# FMCLPCConnector.net
KiCad netlist of a schematic drawn in Altium Designer
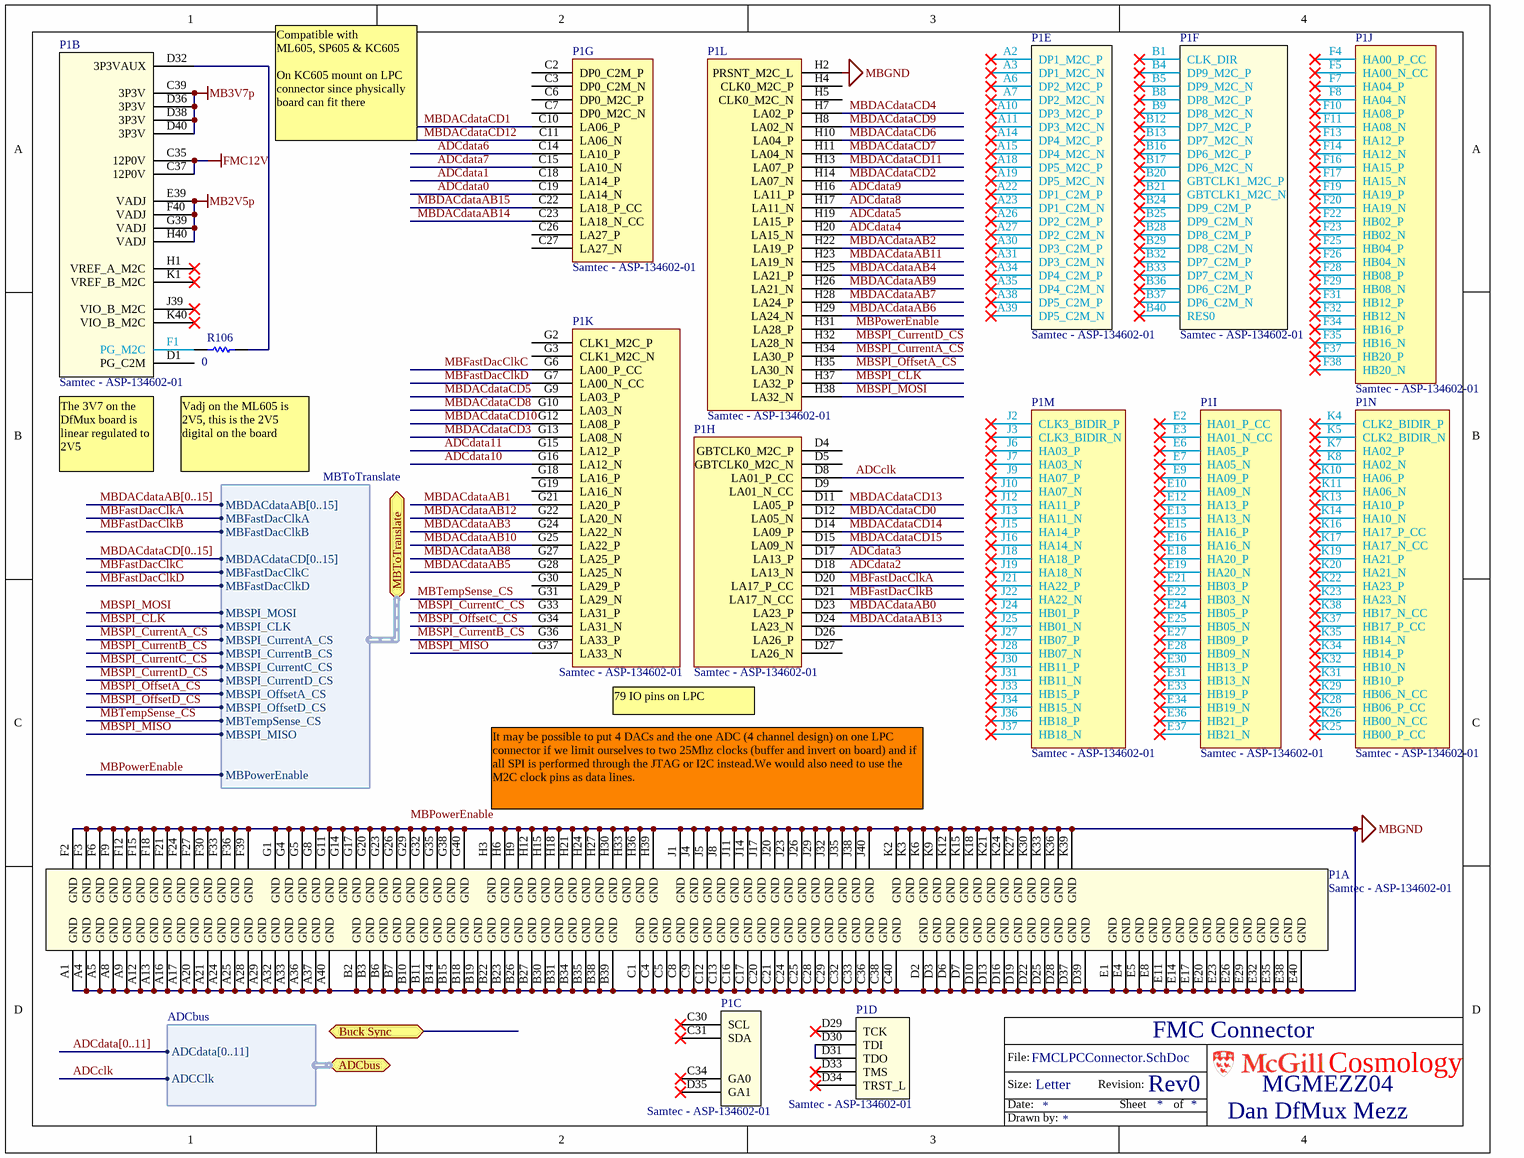
[diagram p0: FMCLPCConnector.SchDoc]

(export (version "E")
  (design (tool "Eeschema 10.0.6"))
  (components
    (comp (ref "P1")
      (value "Samtec - ASP-134602-01")
      (footprint "BTB-SM1-27-2V400M")
      (description "Samtec ASP-134602-01")
      (libsource (lib "MGMEZZ04") (part "Samtec - ASP-134602-01"))
    )
    (comp (ref "R106")
      (value "0")
      (footprint "0603")
      (description "Resistor")
      (fields (field (name "MANUFACTURER") "Generic"))
      (libsource (lib "MGMEZZ04") (part "RES 0603"))
    )
  )
  (nets
    (net (code "3") (name "/ADCclk") (class "Default")
      (node (ref "P1") (pin "D8") (pinfunction "LA01_P_CC_D8") (pintype "passive"))
    )
    (net (code "4") (name "/ADCdata0") (class "Default")
      (node (ref "P1") (pin "C19") (pinfunction "LA14_N_C19") (pintype "passive"))
    )
    (net (code "5") (name "/ADCdata1") (class "Default")
      (node (ref "P1") (pin "C18") (pinfunction "LA14_P_C18") (pintype "passive"))
    )
    (net (code "6") (name "/ADCdata2") (class "Default")
      (node (ref "P1") (pin "D18") (pinfunction "LA13_N_D18") (pintype "passive"))
    )
    (net (code "7") (name "/ADCdata3") (class "Default")
      (node (ref "P1") (pin "D17") (pinfunction "LA13_P_D17") (pintype "passive"))
    )
    (net (code "8") (name "/ADCdata4") (class "Default")
      (node (ref "P1") (pin "H20") (pinfunction "LA15_N_H20") (pintype "passive"))
    )
    (net (code "9") (name "/ADCdata5") (class "Default")
      (node (ref "P1") (pin "H19") (pinfunction "LA15_P_H19") (pintype "passive"))
    )
    (net (code "10") (name "/ADCdata6") (class "Default")
      (node (ref "P1") (pin "C14") (pinfunction "LA10_P_C14") (pintype "passive"))
    )
    (net (code "11") (name "/ADCdata7") (class "Default")
      (node (ref "P1") (pin "C15") (pinfunction "LA10_N_C15") (pintype "passive"))
    )
    (net (code "12") (name "/ADCdata8") (class "Default")
      (node (ref "P1") (pin "H17") (pinfunction "LA11_N_H17") (pintype "passive"))
    )
    (net (code "13") (name "/ADCdata9") (class "Default")
      (node (ref "P1") (pin "H16") (pinfunction "LA11_P_H16") (pintype "passive"))
    )
    (net (code "14") (name "/ADCdata10") (class "Default")
      (node (ref "P1") (pin "G16") (pinfunction "LA12_N_G16") (pintype "passive"))
    )
    (net (code "15") (name "/ADCdata11") (class "Default")
      (node (ref "P1") (pin "G15") (pinfunction "LA12_P_G15") (pintype "passive"))
    )
    (net (code "18") (name "/MBDACdataAB0") (class "Default")
      (node (ref "P1") (pin "D23") (pinfunction "LA23_P_D23") (pintype "passive"))
    )
    (net (code "19") (name "/MBDACdataAB1") (class "Default")
      (node (ref "P1") (pin "G21") (pinfunction "LA20_P_G21") (pintype "passive"))
    )
    (net (code "20") (name "/MBDACdataAB2") (class "Default")
      (node (ref "P1") (pin "H22") (pinfunction "LA19_P_H22") (pintype "passive"))
    )
    (net (code "21") (name "/MBDACdataAB3") (class "Default")
      (node (ref "P1") (pin "G24") (pinfunction "LA22_N_G24") (pintype "passive"))
    )
    (net (code "22") (name "/MBDACdataAB4") (class "Default")
      (node (ref "P1") (pin "H25") (pinfunction "LA21_P_H25") (pintype "passive"))
    )
    (net (code "23") (name "/MBDACdataAB5") (class "Default")
      (node (ref "P1") (pin "G28") (pinfunction "LA25_N_G28") (pintype "passive"))
    )
    (net (code "24") (name "/MBDACdataAB6") (class "Default")
      (node (ref "P1") (pin "H29") (pinfunction "LA24_N_H29") (pintype "passive"))
    )
    (net (code "25") (name "/MBDACdataAB7") (class "Default")
      (node (ref "P1") (pin "H28") (pinfunction "LA24_P_H28") (pintype "passive"))
    )
    (net (code "26") (name "/MBDACdataAB8") (class "Default")
      (node (ref "P1") (pin "G27") (pinfunction "LA25_P_G27") (pintype "passive"))
    )
    (net (code "27") (name "/MBDACdataAB9") (class "Default")
      (node (ref "P1") (pin "H26") (pinfunction "LA21_N_H26") (pintype "passive"))
    )
    (net (code "28") (name "/MBDACdataAB10") (class "Default")
      (node (ref "P1") (pin "G25") (pinfunction "LA22_P_G25") (pintype "passive"))
    )
    (net (code "29") (name "/MBDACdataAB11") (class "Default")
      (node (ref "P1") (pin "H23") (pinfunction "LA19_N_H23") (pintype "passive"))
    )
    (net (code "30") (name "/MBDACdataAB12") (class "Default")
      (node (ref "P1") (pin "G22") (pinfunction "LA20_N_G22") (pintype "passive"))
    )
    (net (code "31") (name "/MBDACdataAB13") (class "Default")
      (node (ref "P1") (pin "D24") (pinfunction "LA23_N_D24") (pintype "passive"))
    )
    (net (code "32") (name "/MBDACdataAB14") (class "Default")
      (node (ref "P1") (pin "C23") (pinfunction "LA18_N_CC_C23") (pintype "passive"))
    )
    (net (code "33") (name "/MBDACdataAB15") (class "Default")
      (node (ref "P1") (pin "C22") (pinfunction "LA18_P_CC_C22") (pintype "passive"))
    )
    (net (code "35") (name "/MBDACdataCD0") (class "Default")
      (node (ref "P1") (pin "D12") (pinfunction "LA05_N_D12") (pintype "passive"))
    )
    (net (code "36") (name "/MBDACdataCD1") (class "Default")
      (node (ref "P1") (pin "C10") (pinfunction "LA06_P_C10") (pintype "passive"))
    )
    (net (code "37") (name "/MBDACdataCD2") (class "Default")
      (node (ref "P1") (pin "H14") (pinfunction "LA07_N_H14") (pintype "passive"))
    )
    (net (code "38") (name "/MBDACdataCD3") (class "Default")
      (node (ref "P1") (pin "G13") (pinfunction "LA08_N_G13") (pintype "passive"))
    )
    (net (code "39") (name "/MBDACdataCD4") (class "Default")
      (node (ref "P1") (pin "H7") (pinfunction "LA02_P_H7") (pintype "passive"))
    )
    (net (code "40") (name "/MBDACdataCD5") (class "Default")
      (node (ref "P1") (pin "G9") (pinfunction "LA03_P_G9") (pintype "passive"))
    )
    (net (code "41") (name "/MBDACdataCD6") (class "Default")
      (node (ref "P1") (pin "H10") (pinfunction "LA04_P_H10") (pintype "passive"))
    )
    (net (code "42") (name "/MBDACdataCD7") (class "Default")
      (node (ref "P1") (pin "H11") (pinfunction "LA04_N_H11") (pintype "passive"))
    )
    (net (code "43") (name "/MBDACdataCD8") (class "Default")
      (node (ref "P1") (pin "G10") (pinfunction "LA03_N_G10") (pintype "passive"))
    )
    (net (code "44") (name "/MBDACdataCD9") (class "Default")
      (node (ref "P1") (pin "H8") (pinfunction "LA02_N_H8") (pintype "passive"))
    )
    (net (code "45") (name "/MBDACdataCD10") (class "Default")
      (node (ref "P1") (pin "G12") (pinfunction "LA08_P_G12") (pintype "passive"))
    )
    (net (code "46") (name "/MBDACdataCD11") (class "Default")
      (node (ref "P1") (pin "H13") (pinfunction "LA07_P_H13") (pintype "passive"))
    )
    (net (code "47") (name "/MBDACdataCD12") (class "Default")
      (node (ref "P1") (pin "C11") (pinfunction "LA06_N_C11") (pintype "passive"))
    )
    (net (code "48") (name "/MBDACdataCD13") (class "Default")
      (node (ref "P1") (pin "D11") (pinfunction "LA05_P_D11") (pintype "passive"))
    )
    (net (code "49") (name "/MBDACdataCD14") (class "Default")
      (node (ref "P1") (pin "D14") (pinfunction "LA09_P_D14") (pintype "passive"))
    )
    (net (code "50") (name "/MBDACdataCD15") (class "Default")
      (node (ref "P1") (pin "D15") (pinfunction "LA09_N_D15") (pintype "passive"))
    )
    (net (code "52") (name "/MBFastDacClkA") (class "Default")
      (node (ref "P1") (pin "D20") (pinfunction "LA17_P_CC_D20") (pintype "passive"))
    )
    (net (code "53") (name "/MBFastDacClkB") (class "Default")
      (node (ref "P1") (pin "D21") (pinfunction "LA17_N_CC_D21") (pintype "passive"))
    )
    (net (code "54") (name "/MBFastDacClkC") (class "Default")
      (node (ref "P1") (pin "G6") (pinfunction "LA00_P_CC_G6") (pintype "passive"))
    )
    (net (code "55") (name "/MBFastDacClkD") (class "Default")
      (node (ref "P1") (pin "G7") (pinfunction "LA00_N_CC_G7") (pintype "passive"))
    )
    (net (code "56") (name "/MBPowerEnable") (class "Default")
      (node (ref "P1") (pin "H31") (pinfunction "LA28_P_H31") (pintype "passive"))
    )
    (net (code "57") (name "/MBSPI_CLK") (class "Default")
      (node (ref "P1") (pin "H37") (pinfunction "LA32_P_H37") (pintype "passive"))
    )
    (net (code "58") (name "/MBSPI_CurrentA_CS") (class "Default")
      (node (ref "P1") (pin "H34") (pinfunction "LA30_P_H34") (pintype "passive"))
    )
    (net (code "59") (name "/MBSPI_CurrentB_CS") (class "Default")
      (node (ref "P1") (pin "G36") (pinfunction "LA33_P_G36") (pintype "passive"))
    )
    (net (code "60") (name "/MBSPI_CurrentC_CS") (class "Default")
      (node (ref "P1") (pin "G33") (pinfunction "LA31_P_G33") (pintype "passive"))
    )
    (net (code "61") (name "/MBSPI_CurrentD_CS") (class "Default")
      (node (ref "P1") (pin "H32") (pinfunction "LA28_N_H32") (pintype "passive"))
    )
    (net (code "62") (name "/MBSPI_MISO") (class "Default")
      (node (ref "P1") (pin "G37") (pinfunction "LA33_N_G37") (pintype "passive"))
    )
    (net (code "63") (name "/MBSPI_MOSI") (class "Default")
      (node (ref "P1") (pin "H38") (pinfunction "LA32_N_H38") (pintype "passive"))
    )
    (net (code "64") (name "/MBSPI_OffsetA_CS") (class "Default")
      (node (ref "P1") (pin "H35") (pinfunction "LA30_N_H35") (pintype "passive"))
    )
    (net (code "65") (name "/MBSPI_OffsetC_CS") (class "Default")
      (node (ref "P1") (pin "G34") (pinfunction "LA31_N_G34") (pintype "passive"))
    )
    (net (code "67") (name "/MBTempSense_CS") (class "Default")
      (node (ref "P1") (pin "G31") (pinfunction "LA29_N_G31") (pintype "passive"))
    )
    (net (code "70") (name "FMC12V") (class "Default")
      (node (ref "P1") (pin "C35") (pinfunction "12P0V_C35") (pintype "passive"))
      (node (ref "P1") (pin "C37") (pinfunction "12P0V_C37") (pintype "passive"))
    )
    (net (code "71") (name "MB2V5p") (class "Default")
      (node (ref "P1") (pin "E39") (pinfunction "VADJ_E39") (pintype "passive"))
      (node (ref "P1") (pin "F40") (pinfunction "VADJ_F40") (pintype "passive"))
      (node (ref "P1") (pin "G39") (pinfunction "VADJ_G39") (pintype "passive"))
      (node (ref "P1") (pin "H40") (pinfunction "VADJ_H40") (pintype "passive"))
    )
    (net (code "72") (name "MB3V7p") (class "Default")
      (node (ref "P1") (pin "C39") (pinfunction "3P3V_C39") (pintype "passive"))
      (node (ref "P1") (pin "D36") (pinfunction "3P3V_D36") (pintype "passive"))
      (node (ref "P1") (pin "D38") (pinfunction "3P3V_D38") (pintype "passive"))
      (node (ref "P1") (pin "D40") (pinfunction "3P3V_D40") (pintype "passive"))
    )
    (net (code "73") (name "MBGND") (class "Default")
      (node (ref "P1") (pin "A1") (pinfunction "GND_A1") (pintype "passive"))
      (node (ref "P1") (pin "A12") (pinfunction "GND_A12") (pintype "passive"))
      (node (ref "P1") (pin "A13") (pinfunction "GND_A13") (pintype "passive"))
      (node (ref "P1") (pin "A16") (pinfunction "GND_A16") (pintype "passive"))
      (node (ref "P1") (pin "A17") (pinfunction "GND_A17") (pintype "passive"))
      (node (ref "P1") (pin "A20") (pinfunction "GND_A20") (pintype "passive"))
      (node (ref "P1") (pin "A21") (pinfunction "GND_A21") (pintype "passive"))
      (node (ref "P1") (pin "A24") (pinfunction "GND_A24") (pintype "passive"))
      (node (ref "P1") (pin "A25") (pinfunction "GND_A25") (pintype "passive"))
      (node (ref "P1") (pin "A28") (pinfunction "GND_A28") (pintype "passive"))
      (node (ref "P1") (pin "A29") (pinfunction "GND_A29") (pintype "passive"))
      (node (ref "P1") (pin "A32") (pinfunction "GND_A32") (pintype "passive"))
      (node (ref "P1") (pin "A33") (pinfunction "GND_A33") (pintype "passive"))
      (node (ref "P1") (pin "A36") (pinfunction "GND_A36") (pintype "passive"))
      (node (ref "P1") (pin "A37") (pinfunction "GND_A37") (pintype "passive"))
      (node (ref "P1") (pin "A4") (pinfunction "GND_A4") (pintype "passive"))
      (node (ref "P1") (pin "A40") (pinfunction "GND_A40") (pintype "passive"))
      (node (ref "P1") (pin "A5") (pinfunction "GND_A5") (pintype "passive"))
      (node (ref "P1") (pin "A8") (pinfunction "GND_A8") (pintype "passive"))
      (node (ref "P1") (pin "A9") (pinfunction "GND_A9") (pintype "passive"))
      (node (ref "P1") (pin "B10") (pinfunction "GND_B10") (pintype "passive"))
      (node (ref "P1") (pin "B11") (pinfunction "GND_B11") (pintype "passive"))
      (node (ref "P1") (pin "B14") (pinfunction "GND_B14") (pintype "passive"))
      (node (ref "P1") (pin "B15") (pinfunction "GND_B15") (pintype "passive"))
      (node (ref "P1") (pin "B18") (pinfunction "GND_B18") (pintype "passive"))
      (node (ref "P1") (pin "B19") (pinfunction "GND_B19") (pintype "passive"))
      (node (ref "P1") (pin "B2") (pinfunction "GND_B2") (pintype "passive"))
      (node (ref "P1") (pin "B22") (pinfunction "GND_B22") (pintype "passive"))
      (node (ref "P1") (pin "B23") (pinfunction "GND_B23") (pintype "passive"))
      (node (ref "P1") (pin "B26") (pinfunction "GND_B26") (pintype "passive"))
      (node (ref "P1") (pin "B27") (pinfunction "GND_B27") (pintype "passive"))
      (node (ref "P1") (pin "B3") (pinfunction "GND_B3") (pintype "passive"))
      (node (ref "P1") (pin "B30") (pinfunction "GND_B30") (pintype "passive"))
      (node (ref "P1") (pin "B31") (pinfunction "GND_B31") (pintype "passive"))
      (node (ref "P1") (pin "B34") (pinfunction "GND_B34") (pintype "passive"))
      (node (ref "P1") (pin "B35") (pinfunction "GND_B35") (pintype "passive"))
      (node (ref "P1") (pin "B38") (pinfunction "GND_B38") (pintype "passive"))
      (node (ref "P1") (pin "B39") (pinfunction "GND_B39") (pintype "passive"))
      (node (ref "P1") (pin "B6") (pinfunction "GND_B6") (pintype "passive"))
      (node (ref "P1") (pin "B7") (pinfunction "GND_B7") (pintype "passive"))
      (node (ref "P1") (pin "C1") (pinfunction "GND_C1") (pintype "passive"))
      (node (ref "P1") (pin "C12") (pinfunction "GND_C12") (pintype "passive"))
      (node (ref "P1") (pin "C13") (pinfunction "GND_C13") (pintype "passive"))
      (node (ref "P1") (pin "C16") (pinfunction "GND_C16") (pintype "passive"))
      (node (ref "P1") (pin "C17") (pinfunction "GND_C17") (pintype "passive"))
      (node (ref "P1") (pin "C20") (pinfunction "GND_C20") (pintype "passive"))
      (node (ref "P1") (pin "C21") (pinfunction "GND_C21") (pintype "passive"))
      (node (ref "P1") (pin "C24") (pinfunction "GND_C24") (pintype "passive"))
      (node (ref "P1") (pin "C25") (pinfunction "GND_C25") (pintype "passive"))
      (node (ref "P1") (pin "C28") (pinfunction "GND_C28") (pintype "passive"))
      (node (ref "P1") (pin "C29") (pinfunction "GND_C29") (pintype "passive"))
      (node (ref "P1") (pin "C32") (pinfunction "GND_C32") (pintype "passive"))
      (node (ref "P1") (pin "C33") (pinfunction "GND_C33") (pintype "passive"))
      (node (ref "P1") (pin "C36") (pinfunction "GND_C36") (pintype "passive"))
      (node (ref "P1") (pin "C38") (pinfunction "GND_C38") (pintype "passive"))
      (node (ref "P1") (pin "C4") (pinfunction "GND_C4") (pintype "passive"))
      (node (ref "P1") (pin "C40") (pinfunction "GND_C40") (pintype "passive"))
      (node (ref "P1") (pin "C5") (pinfunction "GND_C5") (pintype "passive"))
      (node (ref "P1") (pin "C8") (pinfunction "GND_C8") (pintype "passive"))
      (node (ref "P1") (pin "C9") (pinfunction "GND_C9") (pintype "passive"))
      (node (ref "P1") (pin "D10") (pinfunction "GND_D10") (pintype "passive"))
      (node (ref "P1") (pin "D13") (pinfunction "GND_D13") (pintype "passive"))
      (node (ref "P1") (pin "D16") (pinfunction "GND_D16") (pintype "passive"))
      (node (ref "P1") (pin "D19") (pinfunction "GND_D19") (pintype "passive"))
      (node (ref "P1") (pin "D2") (pinfunction "GND_D2") (pintype "passive"))
      (node (ref "P1") (pin "D22") (pinfunction "GND_D22") (pintype "passive"))
      (node (ref "P1") (pin "D25") (pinfunction "GND_D25") (pintype "passive"))
      (node (ref "P1") (pin "D28") (pinfunction "GND_D28") (pintype "passive"))
      (node (ref "P1") (pin "D3") (pinfunction "GND_D3") (pintype "passive"))
      (node (ref "P1") (pin "D37") (pinfunction "GND_D37") (pintype "passive"))
      (node (ref "P1") (pin "D39") (pinfunction "GND_D39") (pintype "passive"))
      (node (ref "P1") (pin "D6") (pinfunction "GND_D6") (pintype "passive"))
      (node (ref "P1") (pin "D7") (pinfunction "GND_D7") (pintype "passive"))
      (node (ref "P1") (pin "E1") (pinfunction "GND_E1") (pintype "passive"))
      (node (ref "P1") (pin "E11") (pinfunction "GND_E11") (pintype "passive"))
      (node (ref "P1") (pin "E14") (pinfunction "GND_E14") (pintype "passive"))
      (node (ref "P1") (pin "E17") (pinfunction "GND_E17") (pintype "passive"))
      (node (ref "P1") (pin "E20") (pinfunction "GND_E20") (pintype "passive"))
      (node (ref "P1") (pin "E23") (pinfunction "GND_E23") (pintype "passive"))
      (node (ref "P1") (pin "E26") (pinfunction "GND_E26") (pintype "passive"))
      (node (ref "P1") (pin "E29") (pinfunction "GND_E29") (pintype "passive"))
      (node (ref "P1") (pin "E32") (pinfunction "GND_E32") (pintype "passive"))
      (node (ref "P1") (pin "E35") (pinfunction "GND_E35") (pintype "passive"))
      (node (ref "P1") (pin "E38") (pinfunction "GND_E38") (pintype "passive"))
      (node (ref "P1") (pin "E4") (pinfunction "GND_E4") (pintype "passive"))
      (node (ref "P1") (pin "E40") (pinfunction "GND_E40") (pintype "passive"))
      (node (ref "P1") (pin "E5") (pinfunction "GND_E5") (pintype "passive"))
      (node (ref "P1") (pin "E8") (pinfunction "GND_E8") (pintype "passive"))
      (node (ref "P1") (pin "F12") (pinfunction "GND_F12") (pintype "passive"))
      (node (ref "P1") (pin "F15") (pinfunction "GND_F15") (pintype "passive"))
      (node (ref "P1") (pin "F18") (pinfunction "GND_F18") (pintype "passive"))
      (node (ref "P1") (pin "F2") (pinfunction "GND_F2") (pintype "passive"))
      (node (ref "P1") (pin "F21") (pinfunction "GND_F21") (pintype "passive"))
      (node (ref "P1") (pin "F24") (pinfunction "GND_F24") (pintype "passive"))
      (node (ref "P1") (pin "F27") (pinfunction "GND_F27") (pintype "passive"))
      (node (ref "P1") (pin "F3") (pinfunction "GND_F3") (pintype "passive"))
      (node (ref "P1") (pin "F30") (pinfunction "GND_F30") (pintype "passive"))
      (node (ref "P1") (pin "F33") (pinfunction "GND_F33") (pintype "passive"))
      (node (ref "P1") (pin "F36") (pinfunction "GND_F36") (pintype "passive"))
      (node (ref "P1") (pin "F39") (pinfunction "GND_F39") (pintype "passive"))
      (node (ref "P1") (pin "F6") (pinfunction "GND_F6") (pintype "passive"))
      (node (ref "P1") (pin "F9") (pinfunction "GND_F9") (pintype "passive"))
      (node (ref "P1") (pin "G1") (pinfunction "GND_G1") (pintype "passive"))
      (node (ref "P1") (pin "G11") (pinfunction "GND_G11") (pintype "passive"))
      (node (ref "P1") (pin "G14") (pinfunction "GND_G14") (pintype "passive"))
      (node (ref "P1") (pin "G17") (pinfunction "GND_G17") (pintype "passive"))
      (node (ref "P1") (pin "G20") (pinfunction "GND_G20") (pintype "passive"))
      (node (ref "P1") (pin "G23") (pinfunction "GND_G23") (pintype "passive"))
      (node (ref "P1") (pin "G26") (pinfunction "GND_G26") (pintype "passive"))
      (node (ref "P1") (pin "G29") (pinfunction "GND_G29") (pintype "passive"))
      (node (ref "P1") (pin "G32") (pinfunction "GND_G32") (pintype "passive"))
      (node (ref "P1") (pin "G35") (pinfunction "GND_G35") (pintype "passive"))
      (node (ref "P1") (pin "G38") (pinfunction "GND_G38") (pintype "passive"))
      (node (ref "P1") (pin "G4") (pinfunction "GND_G4") (pintype "passive"))
      (node (ref "P1") (pin "G40") (pinfunction "GND_G40") (pintype "passive"))
      (node (ref "P1") (pin "G5") (pinfunction "GND_G5") (pintype "passive"))
      (node (ref "P1") (pin "G8") (pinfunction "GND_G8") (pintype "passive"))
      (node (ref "P1") (pin "H12") (pinfunction "GND_H12") (pintype "passive"))
      (node (ref "P1") (pin "H15") (pinfunction "GND_H15") (pintype "passive"))
      (node (ref "P1") (pin "H18") (pinfunction "GND_H18") (pintype "passive"))
      (node (ref "P1") (pin "H2") (pinfunction "PRSNT_M2C_L_H2") (pintype "passive"))
      (node (ref "P1") (pin "H21") (pinfunction "GND_H21") (pintype "passive"))
      (node (ref "P1") (pin "H24") (pinfunction "GND_H24") (pintype "passive"))
      (node (ref "P1") (pin "H27") (pinfunction "GND_H27") (pintype "passive"))
      (node (ref "P1") (pin "H3") (pinfunction "GND_H3") (pintype "passive"))
      (node (ref "P1") (pin "H30") (pinfunction "GND_H30") (pintype "passive"))
      (node (ref "P1") (pin "H33") (pinfunction "GND_H33") (pintype "passive"))
      (node (ref "P1") (pin "H36") (pinfunction "GND_H36") (pintype "passive"))
      (node (ref "P1") (pin "H39") (pinfunction "GND_H39") (pintype "passive"))
      (node (ref "P1") (pin "H6") (pinfunction "GND_H6") (pintype "passive"))
      (node (ref "P1") (pin "H9") (pinfunction "GND_H9") (pintype "passive"))
      (node (ref "P1") (pin "J1") (pinfunction "GND_J1") (pintype "passive"))
      (node (ref "P1") (pin "J11") (pinfunction "GND_J11") (pintype "passive"))
      (node (ref "P1") (pin "J14") (pinfunction "GND_J14") (pintype "passive"))
      (node (ref "P1") (pin "J17") (pinfunction "GND_J17") (pintype "passive"))
      (node (ref "P1") (pin "J20") (pinfunction "GND_J20") (pintype "passive"))
      (node (ref "P1") (pin "J23") (pinfunction "GND_J23") (pintype "passive"))
      (node (ref "P1") (pin "J26") (pinfunction "GND_J26") (pintype "passive"))
      (node (ref "P1") (pin "J29") (pinfunction "GND_J29") (pintype "passive"))
      (node (ref "P1") (pin "J32") (pinfunction "GND_J32") (pintype "passive"))
      (node (ref "P1") (pin "J35") (pinfunction "GND_J35") (pintype "passive"))
      (node (ref "P1") (pin "J38") (pinfunction "GND_J38") (pintype "passive"))
      (node (ref "P1") (pin "J4") (pinfunction "GND_J4") (pintype "passive"))
      (node (ref "P1") (pin "J40") (pinfunction "GND_J40") (pintype "passive"))
      (node (ref "P1") (pin "J5") (pinfunction "GND_J5") (pintype "passive"))
      (node (ref "P1") (pin "J8") (pinfunction "GND_J8") (pintype "passive"))
      (node (ref "P1") (pin "K12") (pinfunction "GND_K12") (pintype "passive"))
      (node (ref "P1") (pin "K15") (pinfunction "GND_K15") (pintype "passive"))
      (node (ref "P1") (pin "K18") (pinfunction "GND_K18") (pintype "passive"))
      (node (ref "P1") (pin "K2") (pinfunction "GND_K2") (pintype "passive"))
      (node (ref "P1") (pin "K21") (pinfunction "GND_K21") (pintype "passive"))
      (node (ref "P1") (pin "K24") (pinfunction "GND_K24") (pintype "passive"))
      (node (ref "P1") (pin "K27") (pinfunction "GND_K27") (pintype "passive"))
      (node (ref "P1") (pin "K3") (pinfunction "GND_K3") (pintype "passive"))
      (node (ref "P1") (pin "K30") (pinfunction "GND_K30") (pintype "passive"))
      (node (ref "P1") (pin "K33") (pinfunction "GND_K33") (pintype "passive"))
      (node (ref "P1") (pin "K36") (pinfunction "GND_K36") (pintype "passive"))
      (node (ref "P1") (pin "K39") (pinfunction "GND_K39") (pintype "passive"))
      (node (ref "P1") (pin "K6") (pinfunction "GND_K6") (pintype "passive"))
      (node (ref "P1") (pin "K9") (pinfunction "GND_K9") (pintype "passive"))
    )
    (net (code "74") (name "Net-(P1B-3P3VAUX)") (class "Default")
      (node (ref "P1") (pin "D32") (pinfunction "3P3VAUX_D32") (pintype "passive"))
      (node (ref "R106") (pin "1") (pinfunction "1_1") (pintype "passive"))
    )
    (net (code "75") (name "Net-(P1B-PG_M2C)") (class "Default")
      (node (ref "P1") (pin "F1") (pinfunction "PG_M2C_F1") (pintype "passive"))
      (node (ref "R106") (pin "2") (pinfunction "2_2") (pintype "passive"))
    )
    (net (code "76") (name "Net-(P1D-TDI)") (class "Default")
      (node (ref "P1") (pin "D30") (pinfunction "TDI_D30") (pintype "passive"))
      (node (ref "P1") (pin "D31") (pinfunction "TDO_D31") (pintype "passive"))
    )
    (net (code "77") (name "unconnected-(P1B-PG_C2M-PadD1)") (class "Default")
      (node (ref "P1") (pin "D1") (pinfunction "PG_C2M_D1") (pintype "passive"))
    )
    (net (code "78") (name "unconnected-(P1B-VIO_B_M2C-PadJ39)") (class "Default")
      (node (ref "P1") (pin "J39") (pinfunction "VIO_B_M2C_J39") (pintype "passive+no_connect"))
    )
    (net (code "79") (name "unconnected-(P1B-VIO_B_M2C-PadK40)") (class "Default")
      (node (ref "P1") (pin "K40") (pinfunction "VIO_B_M2C_K40") (pintype "passive+no_connect"))
    )
    (net (code "80") (name "unconnected-(P1B-VREF_A_M2C-PadH1)") (class "Default")
      (node (ref "P1") (pin "H1") (pinfunction "VREF_A_M2C_H1") (pintype "passive+no_connect"))
    )
    (net (code "81") (name "unconnected-(P1B-VREF_B_M2C-PadK1)") (class "Default")
      (node (ref "P1") (pin "K1") (pinfunction "VREF_B_M2C_K1") (pintype "passive+no_connect"))
    )
    (net (code "82") (name "unconnected-(P1C-GA0-PadC34)") (class "Default")
      (node (ref "P1") (pin "C34") (pinfunction "GA0_C34") (pintype "passive+no_connect"))
    )
    (net (code "83") (name "unconnected-(P1C-GA1-PadD35)") (class "Default")
      (node (ref "P1") (pin "D35") (pinfunction "GA1_D35") (pintype "passive+no_connect"))
    )
    (net (code "84") (name "unconnected-(P1C-SCL-PadC30)") (class "Default")
      (node (ref "P1") (pin "C30") (pinfunction "SCL_C30") (pintype "passive+no_connect"))
    )
    (net (code "85") (name "unconnected-(P1C-SDA-PadC31)") (class "Default")
      (node (ref "P1") (pin "C31") (pinfunction "SDA_C31") (pintype "passive+no_connect"))
    )
    (net (code "86") (name "unconnected-(P1D-TCK-PadD29)") (class "Default")
      (node (ref "P1") (pin "D29") (pinfunction "TCK_D29") (pintype "passive+no_connect"))
    )
    (net (code "87") (name "unconnected-(P1D-TMS-PadD33)") (class "Default")
      (node (ref "P1") (pin "D33") (pinfunction "TMS_D33") (pintype "passive+no_connect"))
    )
    (net (code "88") (name "unconnected-(P1D-TRST_L-PadD34)") (class "Default")
      (node (ref "P1") (pin "D34") (pinfunction "TRST_L_D34") (pintype "passive+no_connect"))
    )
    (net (code "89") (name "unconnected-(P1E-DP1_C2M_N-PadA23)") (class "Default")
      (node (ref "P1") (pin "A23") (pinfunction "DP1_C2M_N_A23") (pintype "passive+no_connect"))
    )
    (net (code "90") (name "unconnected-(P1E-DP1_C2M_P-PadA22)") (class "Default")
      (node (ref "P1") (pin "A22") (pinfunction "DP1_C2M_P_A22") (pintype "passive+no_connect"))
    )
    (net (code "91") (name "unconnected-(P1E-DP1_M2C_N-PadA3)") (class "Default")
      (node (ref "P1") (pin "A3") (pinfunction "DP1_M2C_N_A3") (pintype "passive+no_connect"))
    )
    (net (code "92") (name "unconnected-(P1E-DP1_M2C_P-PadA2)") (class "Default")
      (node (ref "P1") (pin "A2") (pinfunction "DP1_M2C_P_A2") (pintype "passive+no_connect"))
    )
    (net (code "93") (name "unconnected-(P1E-DP2_C2M_N-PadA27)") (class "Default")
      (node (ref "P1") (pin "A27") (pinfunction "DP2_C2M_N_A27") (pintype "passive+no_connect"))
    )
    (net (code "94") (name "unconnected-(P1E-DP2_C2M_P-PadA26)") (class "Default")
      (node (ref "P1") (pin "A26") (pinfunction "DP2_C2M_P_A26") (pintype "passive+no_connect"))
    )
    (net (code "95") (name "unconnected-(P1E-DP2_M2C_N-PadA7)") (class "Default")
      (node (ref "P1") (pin "A7") (pinfunction "DP2_M2C_N_A7") (pintype "passive+no_connect"))
    )
    (net (code "96") (name "unconnected-(P1E-DP2_M2C_P-PadA6)") (class "Default")
      (node (ref "P1") (pin "A6") (pinfunction "DP2_M2C_P_A6") (pintype "passive+no_connect"))
    )
    (net (code "97") (name "unconnected-(P1E-DP3_C2M_N-PadA31)") (class "Default")
      (node (ref "P1") (pin "A31") (pinfunction "DP3_C2M_N_A31") (pintype "passive+no_connect"))
    )
    (net (code "98") (name "unconnected-(P1E-DP3_C2M_P-PadA30)") (class "Default")
      (node (ref "P1") (pin "A30") (pinfunction "DP3_C2M_P_A30") (pintype "passive+no_connect"))
    )
    (net (code "99") (name "unconnected-(P1E-DP3_M2C_N-PadA11)") (class "Default")
      (node (ref "P1") (pin "A11") (pinfunction "DP3_M2C_N_A11") (pintype "passive+no_connect"))
    )
    (net (code "100") (name "unconnected-(P1E-DP3_M2C_P-PadA10)") (class "Default")
      (node (ref "P1") (pin "A10") (pinfunction "DP3_M2C_P_A10") (pintype "passive+no_connect"))
    )
    (net (code "101") (name "unconnected-(P1E-DP4_C2M_N-PadA35)") (class "Default")
      (node (ref "P1") (pin "A35") (pinfunction "DP4_C2M_N_A35") (pintype "passive+no_connect"))
    )
    (net (code "102") (name "unconnected-(P1E-DP4_C2M_P-PadA34)") (class "Default")
      (node (ref "P1") (pin "A34") (pinfunction "DP4_C2M_P_A34") (pintype "passive+no_connect"))
    )
    (net (code "103") (name "unconnected-(P1E-DP4_M2C_N-PadA15)") (class "Default")
      (node (ref "P1") (pin "A15") (pinfunction "DP4_M2C_N_A15") (pintype "passive+no_connect"))
    )
    (net (code "104") (name "unconnected-(P1E-DP4_M2C_P-PadA14)") (class "Default")
      (node (ref "P1") (pin "A14") (pinfunction "DP4_M2C_P_A14") (pintype "passive+no_connect"))
    )
    (net (code "105") (name "unconnected-(P1E-DP5_C2M_N-PadA39)") (class "Default")
      (node (ref "P1") (pin "A39") (pinfunction "DP5_C2M_N_A39") (pintype "passive+no_connect"))
    )
    (net (code "106") (name "unconnected-(P1E-DP5_C2M_P-PadA38)") (class "Default")
      (node (ref "P1") (pin "A38") (pinfunction "DP5_C2M_P_A38") (pintype "passive+no_connect"))
    )
    (net (code "107") (name "unconnected-(P1E-DP5_M2C_N-PadA19)") (class "Default")
      (node (ref "P1") (pin "A19") (pinfunction "DP5_M2C_N_A19") (pintype "passive+no_connect"))
    )
    (net (code "108") (name "unconnected-(P1E-DP5_M2C_P-PadA18)") (class "Default")
      (node (ref "P1") (pin "A18") (pinfunction "DP5_M2C_P_A18") (pintype "passive+no_connect"))
    )
    (net (code "109") (name "unconnected-(P1F-CLK_DIR-PadB1)") (class "Default")
      (node (ref "P1") (pin "B1") (pinfunction "CLK_DIR_B1") (pintype "passive+no_connect"))
    )
    (net (code "110") (name "unconnected-(P1F-DP6_C2M_N-PadB37)") (class "Default")
      (node (ref "P1") (pin "B37") (pinfunction "DP6_C2M_N_B37") (pintype "passive+no_connect"))
    )
    (net (code "111") (name "unconnected-(P1F-DP6_C2M_P-PadB36)") (class "Default")
      (node (ref "P1") (pin "B36") (pinfunction "DP6_C2M_P_B36") (pintype "passive+no_connect"))
    )
    (net (code "112") (name "unconnected-(P1F-DP6_M2C_N-PadB17)") (class "Default")
      (node (ref "P1") (pin "B17") (pinfunction "DP6_M2C_N_B17") (pintype "passive+no_connect"))
    )
    (net (code "113") (name "unconnected-(P1F-DP6_M2C_P-PadB16)") (class "Default")
      (node (ref "P1") (pin "B16") (pinfunction "DP6_M2C_P_B16") (pintype "passive+no_connect"))
    )
    (net (code "114") (name "unconnected-(P1F-DP7_C2M_N-PadB33)") (class "Default")
      (node (ref "P1") (pin "B33") (pinfunction "DP7_C2M_N_B33") (pintype "passive+no_connect"))
    )
    (net (code "115") (name "unconnected-(P1F-DP7_C2M_P-PadB32)") (class "Default")
      (node (ref "P1") (pin "B32") (pinfunction "DP7_C2M_P_B32") (pintype "passive+no_connect"))
    )
    (net (code "116") (name "unconnected-(P1F-DP7_M2C_N-PadB13)") (class "Default")
      (node (ref "P1") (pin "B13") (pinfunction "DP7_M2C_N_B13") (pintype "passive+no_connect"))
    )
    (net (code "117") (name "unconnected-(P1F-DP7_M2C_P-PadB12)") (class "Default")
      (node (ref "P1") (pin "B12") (pinfunction "DP7_M2C_P_B12") (pintype "passive+no_connect"))
    )
    (net (code "118") (name "unconnected-(P1F-DP8_C2M_N-PadB29)") (class "Default")
      (node (ref "P1") (pin "B29") (pinfunction "DP8_C2M_N_B29") (pintype "passive+no_connect"))
    )
    (net (code "119") (name "unconnected-(P1F-DP8_C2M_P-PadB28)") (class "Default")
      (node (ref "P1") (pin "B28") (pinfunction "DP8_C2M_P_B28") (pintype "passive+no_connect"))
    )
    (net (code "120") (name "unconnected-(P1F-DP8_M2C_N-PadB9)") (class "Default")
      (node (ref "P1") (pin "B9") (pinfunction "DP8_M2C_N_B9") (pintype "passive+no_connect"))
    )
    (net (code "121") (name "unconnected-(P1F-DP8_M2C_P-PadB8)") (class "Default")
      (node (ref "P1") (pin "B8") (pinfunction "DP8_M2C_P_B8") (pintype "passive+no_connect"))
    )
    (net (code "122") (name "unconnected-(P1F-DP9_C2M_N-PadB25)") (class "Default")
      (node (ref "P1") (pin "B25") (pinfunction "DP9_C2M_N_B25") (pintype "passive+no_connect"))
    )
    (net (code "123") (name "unconnected-(P1F-DP9_C2M_P-PadB24)") (class "Default")
      (node (ref "P1") (pin "B24") (pinfunction "DP9_C2M_P_B24") (pintype "passive+no_connect"))
    )
    (net (code "124") (name "unconnected-(P1F-DP9_M2C_N-PadB5)") (class "Default")
      (node (ref "P1") (pin "B5") (pinfunction "DP9_M2C_N_B5") (pintype "passive+no_connect"))
    )
    (net (code "125") (name "unconnected-(P1F-DP9_M2C_P-PadB4)") (class "Default")
      (node (ref "P1") (pin "B4") (pinfunction "DP9_M2C_P_B4") (pintype "passive+no_connect"))
    )
    (net (code "126") (name "unconnected-(P1F-GBTCLK1_M2C_N-PadB21)") (class "Default")
      (node (ref "P1") (pin "B21") (pinfunction "GBTCLK1_M2C_N_B21") (pintype "passive+no_connect"))
    )
    (net (code "127") (name "unconnected-(P1F-GBTCLK1_M2C_P-PadB20)") (class "Default")
      (node (ref "P1") (pin "B20") (pinfunction "GBTCLK1_M2C_P_B20") (pintype "passive+no_connect"))
    )
    (net (code "128") (name "unconnected-(P1F-RES0-PadB40)") (class "Default")
      (node (ref "P1") (pin "B40") (pinfunction "RES0_B40") (pintype "passive+no_connect"))
    )
    (net (code "129") (name "unconnected-(P1G-DP0_C2M_N-PadC3)") (class "Default")
      (node (ref "P1") (pin "C3") (pinfunction "DP0_C2M_N_C3") (pintype "passive"))
    )
    (net (code "130") (name "unconnected-(P1G-DP0_C2M_P-PadC2)") (class "Default")
      (node (ref "P1") (pin "C2") (pinfunction "DP0_C2M_P_C2") (pintype "passive"))
    )
    (net (code "131") (name "unconnected-(P1G-DP0_M2C_N-PadC7)") (class "Default")
      (node (ref "P1") (pin "C7") (pinfunction "DP0_M2C_N_C7") (pintype "passive"))
    )
    (net (code "132") (name "unconnected-(P1G-DP0_M2C_P-PadC6)") (class "Default")
      (node (ref "P1") (pin "C6") (pinfunction "DP0_M2C_P_C6") (pintype "passive"))
    )
    (net (code "133") (name "unconnected-(P1G-LA27_N-PadC27)") (class "Default")
      (node (ref "P1") (pin "C27") (pinfunction "LA27_N_C27") (pintype "passive"))
    )
    (net (code "134") (name "unconnected-(P1G-LA27_P-PadC26)") (class "Default")
      (node (ref "P1") (pin "C26") (pinfunction "LA27_P_C26") (pintype "passive"))
    )
    (net (code "135") (name "unconnected-(P1H-GBTCLK0_M2C_N-PadD5)") (class "Default")
      (node (ref "P1") (pin "D5") (pinfunction "GBTCLK0_M2C_N_D5") (pintype "passive"))
    )
    (net (code "136") (name "unconnected-(P1H-GBTCLK0_M2C_P-PadD4)") (class "Default")
      (node (ref "P1") (pin "D4") (pinfunction "GBTCLK0_M2C_P_D4") (pintype "passive"))
    )
    (net (code "137") (name "unconnected-(P1H-LA01_N_CC-PadD9)") (class "Default")
      (node (ref "P1") (pin "D9") (pinfunction "LA01_N_CC_D9") (pintype "passive"))
    )
    (net (code "138") (name "unconnected-(P1H-LA26_N-PadD27)") (class "Default")
      (node (ref "P1") (pin "D27") (pinfunction "LA26_N_D27") (pintype "passive"))
    )
    (net (code "139") (name "unconnected-(P1H-LA26_P-PadD26)") (class "Default")
      (node (ref "P1") (pin "D26") (pinfunction "LA26_P_D26") (pintype "passive"))
    )
    (net (code "140") (name "unconnected-(P1I-HA01_N_CC-PadE3)") (class "Default")
      (node (ref "P1") (pin "E3") (pinfunction "HA01_N_CC_E3") (pintype "passive+no_connect"))
    )
    (net (code "141") (name "unconnected-(P1I-HA01_P_CC-PadE2)") (class "Default")
      (node (ref "P1") (pin "E2") (pinfunction "HA01_P_CC_E2") (pintype "passive+no_connect"))
    )
    (net (code "142") (name "unconnected-(P1I-HA05_N-PadE7)") (class "Default")
      (node (ref "P1") (pin "E7") (pinfunction "HA05_N_E7") (pintype "passive+no_connect"))
    )
    (net (code "143") (name "unconnected-(P1I-HA05_P-PadE6)") (class "Default")
      (node (ref "P1") (pin "E6") (pinfunction "HA05_P_E6") (pintype "passive+no_connect"))
    )
    (net (code "144") (name "unconnected-(P1I-HA09_N-PadE10)") (class "Default")
      (node (ref "P1") (pin "E10") (pinfunction "HA09_N_E10") (pintype "passive+no_connect"))
    )
    (net (code "145") (name "unconnected-(P1I-HA09_P-PadE9)") (class "Default")
      (node (ref "P1") (pin "E9") (pinfunction "HA09_P_E9") (pintype "passive+no_connect"))
    )
    (net (code "146") (name "unconnected-(P1I-HA13_N-PadE13)") (class "Default")
      (node (ref "P1") (pin "E13") (pinfunction "HA13_N_E13") (pintype "passive+no_connect"))
    )
    (net (code "147") (name "unconnected-(P1I-HA13_P-PadE12)") (class "Default")
      (node (ref "P1") (pin "E12") (pinfunction "HA13_P_E12") (pintype "passive+no_connect"))
    )
    (net (code "148") (name "unconnected-(P1I-HA16_N-PadE16)") (class "Default")
      (node (ref "P1") (pin "E16") (pinfunction "HA16_N_E16") (pintype "passive+no_connect"))
    )
    (net (code "149") (name "unconnected-(P1I-HA16_P-PadE15)") (class "Default")
      (node (ref "P1") (pin "E15") (pinfunction "HA16_P_E15") (pintype "passive+no_connect"))
    )
    (net (code "150") (name "unconnected-(P1I-HA20_N-PadE19)") (class "Default")
      (node (ref "P1") (pin "E19") (pinfunction "HA20_N_E19") (pintype "passive+no_connect"))
    )
    (net (code "151") (name "unconnected-(P1I-HA20_P-PadE18)") (class "Default")
      (node (ref "P1") (pin "E18") (pinfunction "HA20_P_E18") (pintype "passive+no_connect"))
    )
    (net (code "152") (name "unconnected-(P1I-HB03_N-PadE22)") (class "Default")
      (node (ref "P1") (pin "E22") (pinfunction "HB03_N_E22") (pintype "passive+no_connect"))
    )
    (net (code "153") (name "unconnected-(P1I-HB03_P-PadE21)") (class "Default")
      (node (ref "P1") (pin "E21") (pinfunction "HB03_P_E21") (pintype "passive+no_connect"))
    )
    (net (code "154") (name "unconnected-(P1I-HB05_N-PadE25)") (class "Default")
      (node (ref "P1") (pin "E25") (pinfunction "HB05_N_E25") (pintype "passive+no_connect"))
    )
    (net (code "155") (name "unconnected-(P1I-HB05_P-PadE24)") (class "Default")
      (node (ref "P1") (pin "E24") (pinfunction "HB05_P_E24") (pintype "passive+no_connect"))
    )
    (net (code "156") (name "unconnected-(P1I-HB09_N-PadE28)") (class "Default")
      (node (ref "P1") (pin "E28") (pinfunction "HB09_N_E28") (pintype "passive+no_connect"))
    )
    (net (code "157") (name "unconnected-(P1I-HB09_P-PadE27)") (class "Default")
      (node (ref "P1") (pin "E27") (pinfunction "HB09_P_E27") (pintype "passive+no_connect"))
    )
    (net (code "158") (name "unconnected-(P1I-HB13_N-PadE31)") (class "Default")
      (node (ref "P1") (pin "E31") (pinfunction "HB13_N_E31") (pintype "passive+no_connect"))
    )
    (net (code "159") (name "unconnected-(P1I-HB13_P-PadE30)") (class "Default")
      (node (ref "P1") (pin "E30") (pinfunction "HB13_P_E30") (pintype "passive+no_connect"))
    )
    (net (code "160") (name "unconnected-(P1I-HB19_N-PadE34)") (class "Default")
      (node (ref "P1") (pin "E34") (pinfunction "HB19_N_E34") (pintype "passive+no_connect"))
    )
    (net (code "161") (name "unconnected-(P1I-HB19_P-PadE33)") (class "Default")
      (node (ref "P1") (pin "E33") (pinfunction "HB19_P_E33") (pintype "passive+no_connect"))
    )
    (net (code "162") (name "unconnected-(P1I-HB21_N-PadE37)") (class "Default")
      (node (ref "P1") (pin "E37") (pinfunction "HB21_N_E37") (pintype "passive+no_connect"))
    )
    (net (code "163") (name "unconnected-(P1I-HB21_P-PadE36)") (class "Default")
      (node (ref "P1") (pin "E36") (pinfunction "HB21_P_E36") (pintype "passive+no_connect"))
    )
    (net (code "164") (name "unconnected-(P1J-HA00_N_CC-PadF5)") (class "Default")
      (node (ref "P1") (pin "F5") (pinfunction "HA00_N_CC_F5") (pintype "passive+no_connect"))
    )
    (net (code "165") (name "unconnected-(P1J-HA00_P_CC-PadF4)") (class "Default")
      (node (ref "P1") (pin "F4") (pinfunction "HA00_P_CC_F4") (pintype "passive+no_connect"))
    )
    (net (code "166") (name "unconnected-(P1J-HA04_N-PadF8)") (class "Default")
      (node (ref "P1") (pin "F8") (pinfunction "HA04_N_F8") (pintype "passive+no_connect"))
    )
    (net (code "167") (name "unconnected-(P1J-HA04_P-PadF7)") (class "Default")
      (node (ref "P1") (pin "F7") (pinfunction "HA04_P_F7") (pintype "passive+no_connect"))
    )
    (net (code "168") (name "unconnected-(P1J-HA08_N-PadF11)") (class "Default")
      (node (ref "P1") (pin "F11") (pinfunction "HA08_N_F11") (pintype "passive+no_connect"))
    )
    (net (code "169") (name "unconnected-(P1J-HA08_P-PadF10)") (class "Default")
      (node (ref "P1") (pin "F10") (pinfunction "HA08_P_F10") (pintype "passive+no_connect"))
    )
    (net (code "170") (name "unconnected-(P1J-HA12_N-PadF14)") (class "Default")
      (node (ref "P1") (pin "F14") (pinfunction "HA12_N_F14") (pintype "passive+no_connect"))
    )
    (net (code "171") (name "unconnected-(P1J-HA12_P-PadF13)") (class "Default")
      (node (ref "P1") (pin "F13") (pinfunction "HA12_P_F13") (pintype "passive+no_connect"))
    )
    (net (code "172") (name "unconnected-(P1J-HA15_N-PadF17)") (class "Default")
      (node (ref "P1") (pin "F17") (pinfunction "HA15_N_F17") (pintype "passive+no_connect"))
    )
    (net (code "173") (name "unconnected-(P1J-HA15_P-PadF16)") (class "Default")
      (node (ref "P1") (pin "F16") (pinfunction "HA15_P_F16") (pintype "passive+no_connect"))
    )
    (net (code "174") (name "unconnected-(P1J-HA19_N-PadF20)") (class "Default")
      (node (ref "P1") (pin "F20") (pinfunction "HA19_N_F20") (pintype "passive+no_connect"))
    )
    (net (code "175") (name "unconnected-(P1J-HA19_P-PadF19)") (class "Default")
      (node (ref "P1") (pin "F19") (pinfunction "HA19_P_F19") (pintype "passive+no_connect"))
    )
    (net (code "176") (name "unconnected-(P1J-HB02_N-PadF23)") (class "Default")
      (node (ref "P1") (pin "F23") (pinfunction "HB02_N_F23") (pintype "passive+no_connect"))
    )
    (net (code "177") (name "unconnected-(P1J-HB02_P-PadF22)") (class "Default")
      (node (ref "P1") (pin "F22") (pinfunction "HB02_P_F22") (pintype "passive+no_connect"))
    )
    (net (code "178") (name "unconnected-(P1J-HB04_N-PadF26)") (class "Default")
      (node (ref "P1") (pin "F26") (pinfunction "HB04_N_F26") (pintype "passive+no_connect"))
    )
    (net (code "179") (name "unconnected-(P1J-HB04_P-PadF25)") (class "Default")
      (node (ref "P1") (pin "F25") (pinfunction "HB04_P_F25") (pintype "passive+no_connect"))
    )
    (net (code "180") (name "unconnected-(P1J-HB08_N-PadF29)") (class "Default")
      (node (ref "P1") (pin "F29") (pinfunction "HB08_N_F29") (pintype "passive+no_connect"))
    )
    (net (code "181") (name "unconnected-(P1J-HB08_P-PadF28)") (class "Default")
      (node (ref "P1") (pin "F28") (pinfunction "HB08_P_F28") (pintype "passive+no_connect"))
    )
    (net (code "182") (name "unconnected-(P1J-HB12_N-PadF32)") (class "Default")
      (node (ref "P1") (pin "F32") (pinfunction "HB12_N_F32") (pintype "passive+no_connect"))
    )
    (net (code "183") (name "unconnected-(P1J-HB12_P-PadF31)") (class "Default")
      (node (ref "P1") (pin "F31") (pinfunction "HB12_P_F31") (pintype "passive+no_connect"))
    )
    (net (code "184") (name "unconnected-(P1J-HB16_N-PadF35)") (class "Default")
      (node (ref "P1") (pin "F35") (pinfunction "HB16_N_F35") (pintype "passive+no_connect"))
    )
    (net (code "185") (name "unconnected-(P1J-HB16_P-PadF34)") (class "Default")
      (node (ref "P1") (pin "F34") (pinfunction "HB16_P_F34") (pintype "passive+no_connect"))
    )
    (net (code "186") (name "unconnected-(P1J-HB20_N-PadF38)") (class "Default")
      (node (ref "P1") (pin "F38") (pinfunction "HB20_N_F38") (pintype "passive+no_connect"))
    )
    (net (code "187") (name "unconnected-(P1J-HB20_P-PadF37)") (class "Default")
      (node (ref "P1") (pin "F37") (pinfunction "HB20_P_F37") (pintype "passive+no_connect"))
    )
    (net (code "188") (name "unconnected-(P1K-CLK1_M2C_N-PadG3)") (class "Default")
      (node (ref "P1") (pin "G3") (pinfunction "CLK1_M2C_N_G3") (pintype "passive"))
    )
    (net (code "189") (name "unconnected-(P1K-CLK1_M2C_P-PadG2)") (class "Default")
      (node (ref "P1") (pin "G2") (pinfunction "CLK1_M2C_P_G2") (pintype "passive"))
    )
    (net (code "190") (name "unconnected-(P1K-LA16_N-PadG19)") (class "Default")
      (node (ref "P1") (pin "G19") (pinfunction "LA16_N_G19") (pintype "passive"))
    )
    (net (code "191") (name "unconnected-(P1K-LA16_P-PadG18)") (class "Default")
      (node (ref "P1") (pin "G18") (pinfunction "LA16_P_G18") (pintype "passive"))
    )
    (net (code "192") (name "unconnected-(P1K-LA29_P-PadG30)") (class "Default")
      (node (ref "P1") (pin "G30") (pinfunction "LA29_P_G30") (pintype "passive"))
    )
    (net (code "193") (name "unconnected-(P1L-CLK0_M2C_N-PadH5)") (class "Default")
      (node (ref "P1") (pin "H5") (pinfunction "CLK0_M2C_N_H5") (pintype "passive"))
    )
    (net (code "194") (name "unconnected-(P1L-CLK0_M2C_P-PadH4)") (class "Default")
      (node (ref "P1") (pin "H4") (pinfunction "CLK0_M2C_P_H4") (pintype "passive"))
    )
    (net (code "195") (name "unconnected-(P1M-CLK3_BIDIR_N-PadJ3)") (class "Default")
      (node (ref "P1") (pin "J3") (pinfunction "CLK3_BIDIR_N_J3") (pintype "passive+no_connect"))
    )
    (net (code "196") (name "unconnected-(P1M-CLK3_BIDIR_P-PadJ2)") (class "Default")
      (node (ref "P1") (pin "J2") (pinfunction "CLK3_BIDIR_P_J2") (pintype "passive+no_connect"))
    )
    (net (code "197") (name "unconnected-(P1M-HA03_N-PadJ7)") (class "Default")
      (node (ref "P1") (pin "J7") (pinfunction "HA03_N_J7") (pintype "passive+no_connect"))
    )
    (net (code "198") (name "unconnected-(P1M-HA03_P-PadJ6)") (class "Default")
      (node (ref "P1") (pin "J6") (pinfunction "HA03_P_J6") (pintype "passive+no_connect"))
    )
    (net (code "199") (name "unconnected-(P1M-HA07_N-PadJ10)") (class "Default")
      (node (ref "P1") (pin "J10") (pinfunction "HA07_N_J10") (pintype "passive+no_connect"))
    )
    (net (code "200") (name "unconnected-(P1M-HA07_P-PadJ9)") (class "Default")
      (node (ref "P1") (pin "J9") (pinfunction "HA07_P_J9") (pintype "passive+no_connect"))
    )
    (net (code "201") (name "unconnected-(P1M-HA11_N-PadJ13)") (class "Default")
      (node (ref "P1") (pin "J13") (pinfunction "HA11_N_J13") (pintype "passive+no_connect"))
    )
    (net (code "202") (name "unconnected-(P1M-HA11_P-PadJ12)") (class "Default")
      (node (ref "P1") (pin "J12") (pinfunction "HA11_P_J12") (pintype "passive+no_connect"))
    )
    (net (code "203") (name "unconnected-(P1M-HA14_N-PadJ16)") (class "Default")
      (node (ref "P1") (pin "J16") (pinfunction "HA14_N_J16") (pintype "passive+no_connect"))
    )
    (net (code "204") (name "unconnected-(P1M-HA14_P-PadJ15)") (class "Default")
      (node (ref "P1") (pin "J15") (pinfunction "HA14_P_J15") (pintype "passive+no_connect"))
    )
    (net (code "205") (name "unconnected-(P1M-HA18_N-PadJ19)") (class "Default")
      (node (ref "P1") (pin "J19") (pinfunction "HA18_N_J19") (pintype "passive+no_connect"))
    )
    (net (code "206") (name "unconnected-(P1M-HA18_P-PadJ18)") (class "Default")
      (node (ref "P1") (pin "J18") (pinfunction "HA18_P_J18") (pintype "passive+no_connect"))
    )
    (net (code "207") (name "unconnected-(P1M-HA22_N-PadJ22)") (class "Default")
      (node (ref "P1") (pin "J22") (pinfunction "HA22_N_J22") (pintype "passive+no_connect"))
    )
    (net (code "208") (name "unconnected-(P1M-HA22_P-PadJ21)") (class "Default")
      (node (ref "P1") (pin "J21") (pinfunction "HA22_P_J21") (pintype "passive+no_connect"))
    )
    (net (code "209") (name "unconnected-(P1M-HB01_N-PadJ25)") (class "Default")
      (node (ref "P1") (pin "J25") (pinfunction "HB01_N_J25") (pintype "passive+no_connect"))
    )
    (net (code "210") (name "unconnected-(P1M-HB01_P-PadJ24)") (class "Default")
      (node (ref "P1") (pin "J24") (pinfunction "HB01_P_J24") (pintype "passive+no_connect"))
    )
    (net (code "211") (name "unconnected-(P1M-HB07_N-PadJ28)") (class "Default")
      (node (ref "P1") (pin "J28") (pinfunction "HB07_N_J28") (pintype "passive+no_connect"))
    )
    (net (code "212") (name "unconnected-(P1M-HB07_P-PadJ27)") (class "Default")
      (node (ref "P1") (pin "J27") (pinfunction "HB07_P_J27") (pintype "passive+no_connect"))
    )
    (net (code "213") (name "unconnected-(P1M-HB11_N-PadJ31)") (class "Default")
      (node (ref "P1") (pin "J31") (pinfunction "HB11_N_J31") (pintype "passive+no_connect"))
    )
    (net (code "214") (name "unconnected-(P1M-HB11_P-PadJ30)") (class "Default")
      (node (ref "P1") (pin "J30") (pinfunction "HB11_P_J30") (pintype "passive+no_connect"))
    )
    (net (code "215") (name "unconnected-(P1M-HB15_N-PadJ34)") (class "Default")
      (node (ref "P1") (pin "J34") (pinfunction "HB15_N_J34") (pintype "passive+no_connect"))
    )
    (net (code "216") (name "unconnected-(P1M-HB15_P-PadJ33)") (class "Default")
      (node (ref "P1") (pin "J33") (pinfunction "HB15_P_J33") (pintype "passive+no_connect"))
    )
    (net (code "217") (name "unconnected-(P1M-HB18_N-PadJ37)") (class "Default")
      (node (ref "P1") (pin "J37") (pinfunction "HB18_N_J37") (pintype "passive+no_connect"))
    )
    (net (code "218") (name "unconnected-(P1M-HB18_P-PadJ36)") (class "Default")
      (node (ref "P1") (pin "J36") (pinfunction "HB18_P_J36") (pintype "passive+no_connect"))
    )
    (net (code "219") (name "unconnected-(P1N-CLK2_BIDIR_N-PadK5)") (class "Default")
      (node (ref "P1") (pin "K5") (pinfunction "CLK2_BIDIR_N_K5") (pintype "passive+no_connect"))
    )
    (net (code "220") (name "unconnected-(P1N-CLK2_BIDIR_P-PadK4)") (class "Default")
      (node (ref "P1") (pin "K4") (pinfunction "CLK2_BIDIR_P_K4") (pintype "passive+no_connect"))
    )
    (net (code "221") (name "unconnected-(P1N-HA02_N-PadK8)") (class "Default")
      (node (ref "P1") (pin "K8") (pinfunction "HA02_N_K8") (pintype "passive+no_connect"))
    )
    (net (code "222") (name "unconnected-(P1N-HA02_P-PadK7)") (class "Default")
      (node (ref "P1") (pin "K7") (pinfunction "HA02_P_K7") (pintype "passive+no_connect"))
    )
    (net (code "223") (name "unconnected-(P1N-HA06_N-PadK11)") (class "Default")
      (node (ref "P1") (pin "K11") (pinfunction "HA06_N_K11") (pintype "passive+no_connect"))
    )
    (net (code "224") (name "unconnected-(P1N-HA06_P-PadK10)") (class "Default")
      (node (ref "P1") (pin "K10") (pinfunction "HA06_P_K10") (pintype "passive+no_connect"))
    )
    (net (code "225") (name "unconnected-(P1N-HA10_N-PadK14)") (class "Default")
      (node (ref "P1") (pin "K14") (pinfunction "HA10_N_K14") (pintype "passive+no_connect"))
    )
    (net (code "226") (name "unconnected-(P1N-HA10_P-PadK13)") (class "Default")
      (node (ref "P1") (pin "K13") (pinfunction "HA10_P_K13") (pintype "passive+no_connect"))
    )
    (net (code "227") (name "unconnected-(P1N-HA17_N_CC-PadK17)") (class "Default")
      (node (ref "P1") (pin "K17") (pinfunction "HA17_N_CC_K17") (pintype "passive+no_connect"))
    )
    (net (code "228") (name "unconnected-(P1N-HA17_P_CC-PadK16)") (class "Default")
      (node (ref "P1") (pin "K16") (pinfunction "HA17_P_CC_K16") (pintype "passive+no_connect"))
    )
    (net (code "229") (name "unconnected-(P1N-HA21_N-PadK20)") (class "Default")
      (node (ref "P1") (pin "K20") (pinfunction "HA21_N_K20") (pintype "passive+no_connect"))
    )
    (net (code "230") (name "unconnected-(P1N-HA21_P-PadK19)") (class "Default")
      (node (ref "P1") (pin "K19") (pinfunction "HA21_P_K19") (pintype "passive+no_connect"))
    )
    (net (code "231") (name "unconnected-(P1N-HA23_N-PadK23)") (class "Default")
      (node (ref "P1") (pin "K23") (pinfunction "HA23_N_K23") (pintype "passive+no_connect"))
    )
    (net (code "232") (name "unconnected-(P1N-HA23_P-PadK22)") (class "Default")
      (node (ref "P1") (pin "K22") (pinfunction "HA23_P_K22") (pintype "passive+no_connect"))
    )
    (net (code "233") (name "unconnected-(P1N-HB00_N_CC-PadK26)") (class "Default")
      (node (ref "P1") (pin "K26") (pinfunction "HB00_N_CC_K26") (pintype "passive+no_connect"))
    )
    (net (code "234") (name "unconnected-(P1N-HB00_P_CC-PadK25)") (class "Default")
      (node (ref "P1") (pin "K25") (pinfunction "HB00_P_CC_K25") (pintype "passive+no_connect"))
    )
    (net (code "235") (name "unconnected-(P1N-HB06_N_CC-PadK29)") (class "Default")
      (node (ref "P1") (pin "K29") (pinfunction "HB06_N_CC_K29") (pintype "passive+no_connect"))
    )
    (net (code "236") (name "unconnected-(P1N-HB06_P_CC-PadK28)") (class "Default")
      (node (ref "P1") (pin "K28") (pinfunction "HB06_P_CC_K28") (pintype "passive+no_connect"))
    )
    (net (code "237") (name "unconnected-(P1N-HB10_N-PadK32)") (class "Default")
      (node (ref "P1") (pin "K32") (pinfunction "HB10_N_K32") (pintype "passive+no_connect"))
    )
    (net (code "238") (name "unconnected-(P1N-HB10_P-PadK31)") (class "Default")
      (node (ref "P1") (pin "K31") (pinfunction "HB10_P_K31") (pintype "passive+no_connect"))
    )
    (net (code "239") (name "unconnected-(P1N-HB14_N-PadK35)") (class "Default")
      (node (ref "P1") (pin "K35") (pinfunction "HB14_N_K35") (pintype "passive+no_connect"))
    )
    (net (code "240") (name "unconnected-(P1N-HB14_P-PadK34)") (class "Default")
      (node (ref "P1") (pin "K34") (pinfunction "HB14_P_K34") (pintype "passive+no_connect"))
    )
    (net (code "241") (name "unconnected-(P1N-HB17_N_CC-PadK38)") (class "Default")
      (node (ref "P1") (pin "K38") (pinfunction "HB17_N_CC_K38") (pintype "passive+no_connect"))
    )
    (net (code "242") (name "unconnected-(P1N-HB17_P_CC-PadK37)") (class "Default")
      (node (ref "P1") (pin "K37") (pinfunction "HB17_P_CC_K37") (pintype "passive+no_connect"))
    )
  )
)
